# Controller.net
KiCad netlist of a schematic drawn in Altium Designer
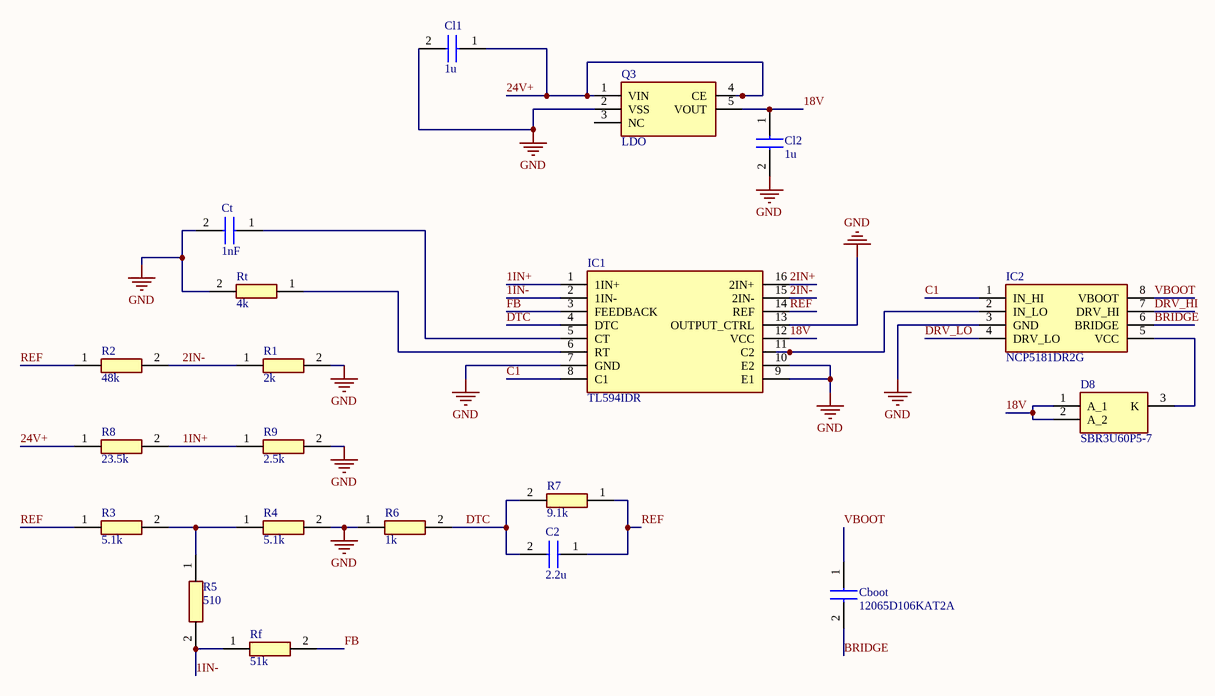
[diagram p0: Controller.SchDoc]

(export (version "E")
  (design (tool "Eeschema 10.0.6"))
  (components
    (comp (ref "C2")
      (value "2.2u")
      (footprint "SamacSys:CAPC1005X55N")
      (description "Capacitor")
      (fields
        (field (name "MANUFACTURER_PART_NUMBER") "C0402C225K9PACTU")
        (field (name "MOUSER PART NUMBER") "80-C0402C225K9P")
      )
      (libsource (lib "*") (part "C0402C225K9PACTU"))
    )
    (comp (ref "Cboot")
      (value "12065D106KAT2A")
      (footprint "SamacSys:CAPC3216X229N")
      (description "Capacitor")
      (fields (field (name "MOUSER PART NUMBER") "581-12065D106KAT2A"))
      (libsource (lib "*") (part "12065D106KAT2A"))
    )
    (comp (ref "Cl1")
      (value "1u")
      (footprint "SamacSys:CAPC3225X105N")
      (description "Capacitor")
      (fields
        (field (name "MANUFACTURER_PART_NUMBER") "885012209047")
        (field (name "MOUSER PART NUMBER") "710-885012209047")
      )
      (libsource (lib "*") (part "885012209047"))
    )
    (comp (ref "Cl2")
      (value "1u")
      (footprint "SamacSys:CAPC3225X105N")
      (description "Capacitor")
      (fields
        (field (name "MANUFACTURER_PART_NUMBER") "885012209047")
        (field (name "MOUSER PART NUMBER") "710-885012209047")
      )
      (libsource (lib "*") (part "885012209047"))
    )
    (comp (ref "Ct")
      (value "1nF")
      (footprint "SamacSys:CAPC1608X90N")
      (description "Capacitor")
      (fields
        (field (name "MANUFACTURER_PART_NUMBER") "06031C102KAZ2A")
        (field (name "MOUSER PART NUMBER") "581-06031C102KAZ2A")
      )
      (libsource (lib "*") (part "06031C102KAZ2A"))
    )
    (comp (ref "D8")
      (value "SBR3U60P5-7")
      (footprint "SamacSys:SBR3U60P57")
      (description "Schottky Diode")
      (fields (field (name "MOUSER PART NUMBER") "621-SBR3U60P5-7"))
      (libsource (lib "*") (part "SBR3U60P5-7"))
    )
    (comp (ref "IC1")
      (value "TL594IDR")
      (footprint "SamacSys:SOIC127P600X175-16N")
      (description "Integrated Circuit")
      (fields (field (name "MOUSER PART NUMBER") "595-TL594IDR"))
      (libsource (lib "*") (part "TL594IDR"))
    )
    (comp (ref "IC2")
      (value "NCP5181DR2G")
      (footprint "SamacSys:SOIC127P600X175-8N")
      (description "Integrated Circuit")
      (fields (field (name "MOUSER PART NUMBER") "863-NCP5181DR2G"))
      (libsource (lib "*") (part "NCP5181DR2G"))
    )
    (comp (ref "Q3")
      (value "LDO")
      (footprint "SamacSys:SOT95P280X120-5N")
      (description "Transistor")
      (fields
        (field (name "MANUFACTURER_PART_NUMBER") "XC6210B302MR-G")
        (field (name "MOUSER PART NUMBER") "865-XC6210B302MR-G")
      )
      (libsource (lib "*") (part "XC6210B302MR-G"))
    )
    (comp (ref "R1")
      (value "2k")
      (footprint "SamacSys:RESC1608X55N")
      (description "Resistor")
      (fields (field (name "MANUFACTURER_PART_NUMBER") "RCA060310R0FKEAHP"))
      (libsource (lib "*") (part "RCA060310R0FKEAHP"))
    )
    (comp (ref "R2")
      (value "48k")
      (footprint "SamacSys:RESC2012X65N")
      (description "Resistor")
      (fields
        (field (name "MANUFACTURER_PART_NUMBER") "CPF0805B49K9E1")
        (field (name "MOUSER PART NUMBER") "279-CPF0805B49K9E1")
      )
      (libsource (lib "*") (part "CPF0805B49K9E1"))
    )
    (comp (ref "R3")
      (value "5.1k")
      (footprint "SamacSys:RESC1005X40N")
      (description "Resistor")
      (fields
        (field (name "MANUFACTURER_PART_NUMBER") "CRCW04025K10JNED")
        (field (name "MOUSER PART NUMBER") "71-CRCW0402J-5.1K-E3")
      )
      (libsource (lib "*") (part "CRCW04025K10JNED"))
    )
    (comp (ref "R4")
      (value "5.1k")
      (footprint "SamacSys:RESC1005X40N")
      (description "Resistor")
      (fields
        (field (name "MANUFACTURER_PART_NUMBER") "CRCW04025K10JNED")
        (field (name "MOUSER PART NUMBER") "71-CRCW0402J-5.1K-E3")
      )
      (libsource (lib "*") (part "CRCW04025K10JNED"))
    )
    (comp (ref "R5")
      (value "510")
      (footprint "SamacSys:RESC1608X50N")
      (description "Resistor")
      (fields
        (field (name "MANUFACTURER_PART_NUMBER") "CRCW0603510RJNEA")
        (field (name "MOUSER PART NUMBER") "71-CRCW0603J-510-E3")
      )
      (libsource (lib "*") (part "CRCW0603510RJNEA"))
    )
    (comp (ref "R6")
      (value "1k")
      (footprint "SamacSys:RESC1608X55N")
      (description "Resistor")
      (fields (field (name "MANUFACTURER_PART_NUMBER") "RCA060310R0FKEAHP"))
      (libsource (lib "*") (part "RCA060310R0FKEAHP"))
    )
    (comp (ref "R7")
      (value "9.1k")
      (footprint "SamacSys:RESC1005X40N")
      (description "Resistor")
      (fields
        (field (name "MANUFACTURER_PART_NUMBER") "CRCW04029K10JNED")
        (field (name "MOUSER PART NUMBER") "71-CRCW0402J-9.1K-E3")
      )
      (libsource (lib "*") (part "CRCW04029K10JNED"))
    )
    (comp (ref "R8")
      (value "23.5k")
      (footprint "SamacSys:RESC1608X55N")
      (description "Resistor")
      (fields (field (name "MANUFACTURER_PART_NUMBER") "MCT06030C2352FP500"))
      (libsource (lib "") (part "MCT06030C2352FP500_1"))
    )
    (comp (ref "R9")
      (value "2.5k")
      (footprint "SamacSys:RESC2012X60N")
      (description "Resistor")
      (fields
        (field (name "MANUFACTURER_PART_NUMBER") "RN732ATTD2501B25")
        (field (name "MOUSER PART NUMBER") "660-RN732ATTD2501B25")
      )
      (libsource (lib "*") (part "RN732ATTD2501B25"))
    )
    (comp (ref "Rf")
      (value "51k")
      (footprint "SamacSys:RESC1005X40N")
      (description "Resistor")
      (fields (field (name "MANUFACTURER_PART_NUMBER") "MCMR04X5102FTL"))
      (libsource (lib "*") (part "MCMR04X5102FTL"))
    )
    (comp (ref "Rt")
      (value "4k")
      (footprint "SamacSys:RESC1608X55N")
      (description "Resistor")
      (fields (field (name "MANUFACTURER_PART_NUMBER") "MCT06030C2352FP500"))
      (libsource (lib "*") (part "MCT06030C2352FP500"))
    )
  )
  (nets
    (net (code "1") (name "/1IN+") (class "Default")
      (node (ref "IC1") (pin "1") (pinfunction "1IN+_1") (pintype "passive"))
      (node (ref "R8") (pin "2") (pinfunction "2_2") (pintype "passive"))
      (node (ref "R9") (pin "1") (pinfunction "1_1") (pintype "passive"))
    )
    (net (code "2") (name "/1IN-") (class "Default")
      (node (ref "IC1") (pin "2") (pinfunction "1IN-_2") (pintype "passive"))
      (node (ref "R5") (pin "2") (pinfunction "2_2") (pintype "passive"))
      (node (ref "Rf") (pin "1") (pinfunction "1_1") (pintype "passive"))
    )
    (net (code "3") (name "/2IN+") (class "Default")
      (node (ref "IC1") (pin "16") (pinfunction "2IN+_16") (pintype "passive"))
    )
    (net (code "4") (name "/2IN-") (class "Default")
      (node (ref "IC1") (pin "15") (pinfunction "2IN-_15") (pintype "passive"))
      (node (ref "R1") (pin "1") (pinfunction "1_1") (pintype "passive"))
      (node (ref "R2") (pin "2") (pinfunction "2_2") (pintype "passive"))
    )
    (net (code "5") (name "/18V") (class "Default")
      (node (ref "Cl2") (pin "1") (pinfunction "1_1") (pintype "passive"))
      (node (ref "D8") (pin "1") (pinfunction "A_1_1") (pintype "passive"))
      (node (ref "D8") (pin "2") (pinfunction "A_2_2") (pintype "passive"))
      (node (ref "IC1") (pin "12") (pinfunction "VCC_12") (pintype "passive"))
      (node (ref "Q3") (pin "5") (pinfunction "VOUT_5") (pintype "passive"))
    )
    (net (code "6") (name "/24V+") (class "Default")
      (node (ref "Cl1") (pin "1") (pinfunction "1_1") (pintype "passive"))
      (node (ref "Q3") (pin "1") (pinfunction "VIN_1") (pintype "passive"))
      (node (ref "Q3") (pin "4") (pinfunction "CE_4") (pintype "passive"))
      (node (ref "R8") (pin "1") (pinfunction "1_1") (pintype "passive"))
    )
    (net (code "7") (name "/BRIDGE") (class "Default")
      (node (ref "Cboot") (pin "2") (pinfunction "2_2") (pintype "passive"))
      (node (ref "IC2") (pin "6") (pinfunction "BRIDGE_6") (pintype "passive"))
    )
    (net (code "8") (name "/C1") (class "Default")
      (node (ref "IC1") (pin "8") (pinfunction "C1_8") (pintype "passive"))
      (node (ref "IC2") (pin "1") (pinfunction "IN_HI_1") (pintype "passive"))
    )
    (net (code "9") (name "/DRV_HI") (class "Default")
      (node (ref "IC2") (pin "7") (pinfunction "DRV_HI_7") (pintype "passive"))
    )
    (net (code "10") (name "/DRV_LO") (class "Default")
      (node (ref "IC2") (pin "4") (pinfunction "DRV_LO_4") (pintype "passive"))
    )
    (net (code "11") (name "/DTC") (class "Default")
      (node (ref "C2") (pin "2") (pinfunction "2_2") (pintype "passive"))
      (node (ref "IC1") (pin "4") (pinfunction "DTC_4") (pintype "passive"))
      (node (ref "R6") (pin "2") (pinfunction "2_2") (pintype "passive"))
      (node (ref "R7") (pin "2") (pinfunction "2_2") (pintype "passive"))
    )
    (net (code "12") (name "/FB") (class "Default")
      (node (ref "IC1") (pin "3") (pinfunction "FEEDBACK_3") (pintype "passive"))
      (node (ref "Rf") (pin "2") (pinfunction "2_2") (pintype "passive"))
    )
    (net (code "13") (name "/REF") (class "Default")
      (node (ref "C2") (pin "1") (pinfunction "1_1") (pintype "passive"))
      (node (ref "IC1") (pin "14") (pinfunction "REF_14") (pintype "passive"))
      (node (ref "R2") (pin "1") (pinfunction "1_1") (pintype "passive"))
      (node (ref "R3") (pin "1") (pinfunction "1_1") (pintype "passive"))
      (node (ref "R7") (pin "1") (pinfunction "1_1") (pintype "passive"))
    )
    (net (code "14") (name "/VBOOT") (class "Default")
      (node (ref "Cboot") (pin "1") (pinfunction "1_1") (pintype "passive"))
      (node (ref "IC2") (pin "8") (pinfunction "VBOOT_8") (pintype "passive"))
    )
    (net (code "15") (name "GND") (class "Default")
      (node (ref "Cl1") (pin "2") (pinfunction "2_2") (pintype "passive"))
      (node (ref "Cl2") (pin "2") (pinfunction "2_2") (pintype "passive"))
      (node (ref "Ct") (pin "2") (pinfunction "2_2") (pintype "passive"))
      (node (ref "IC1") (pin "10") (pinfunction "E2_10") (pintype "passive"))
      (node (ref "IC1") (pin "13") (pinfunction "OUTPUT_CTRL_13") (pintype "passive"))
      (node (ref "IC1") (pin "7") (pinfunction "GND_7") (pintype "passive"))
      (node (ref "IC1") (pin "9") (pinfunction "E1_9") (pintype "passive"))
      (node (ref "IC2") (pin "3") (pinfunction "GND_3") (pintype "passive"))
      (node (ref "Q3") (pin "2") (pinfunction "VSS_2") (pintype "passive"))
      (node (ref "R1") (pin "2") (pinfunction "2_2") (pintype "passive"))
      (node (ref "R4") (pin "2") (pinfunction "2_2") (pintype "passive"))
      (node (ref "R6") (pin "1") (pinfunction "1_1") (pintype "passive"))
      (node (ref "R9") (pin "2") (pinfunction "2_2") (pintype "passive"))
      (node (ref "Rt") (pin "2") (pinfunction "2_2") (pintype "passive"))
    )
    (net (code "16") (name "Net-(D8-K)") (class "Default")
      (node (ref "D8") (pin "3") (pinfunction "K_3") (pintype "passive"))
      (node (ref "IC2") (pin "5") (pinfunction "VCC_5") (pintype "passive"))
    )
    (net (code "17") (name "Net-(IC1-C2)") (class "Default")
      (node (ref "IC1") (pin "11") (pinfunction "C2_11") (pintype "passive"))
      (node (ref "IC2") (pin "2") (pinfunction "IN_LO_2") (pintype "passive"))
    )
    (net (code "18") (name "Net-(IC1-CT)") (class "Default")
      (node (ref "Ct") (pin "1") (pinfunction "1_1") (pintype "passive"))
      (node (ref "IC1") (pin "5") (pinfunction "CT_5") (pintype "passive"))
    )
    (net (code "19") (name "Net-(IC1-RT)") (class "Default")
      (node (ref "IC1") (pin "6") (pinfunction "RT_6") (pintype "passive"))
      (node (ref "Rt") (pin "1") (pinfunction "1_1") (pintype "passive"))
    )
    (net (code "20") (name "Net-(R3-Pad2)") (class "Default")
      (node (ref "R3") (pin "2") (pinfunction "2_2") (pintype "passive"))
      (node (ref "R4") (pin "1") (pinfunction "1_1") (pintype "passive"))
      (node (ref "R5") (pin "1") (pinfunction "1_1") (pintype "passive"))
    )
    (net (code "21") (name "unconnected-(Q3-NC-Pad3)") (class "Default")
      (node (ref "Q3") (pin "3") (pinfunction "NC_3") (pintype "passive"))
    )
  )
)
